# gps-breakout-mk-1_3.net
KiCad netlist of a schematic drawn in EAGLE
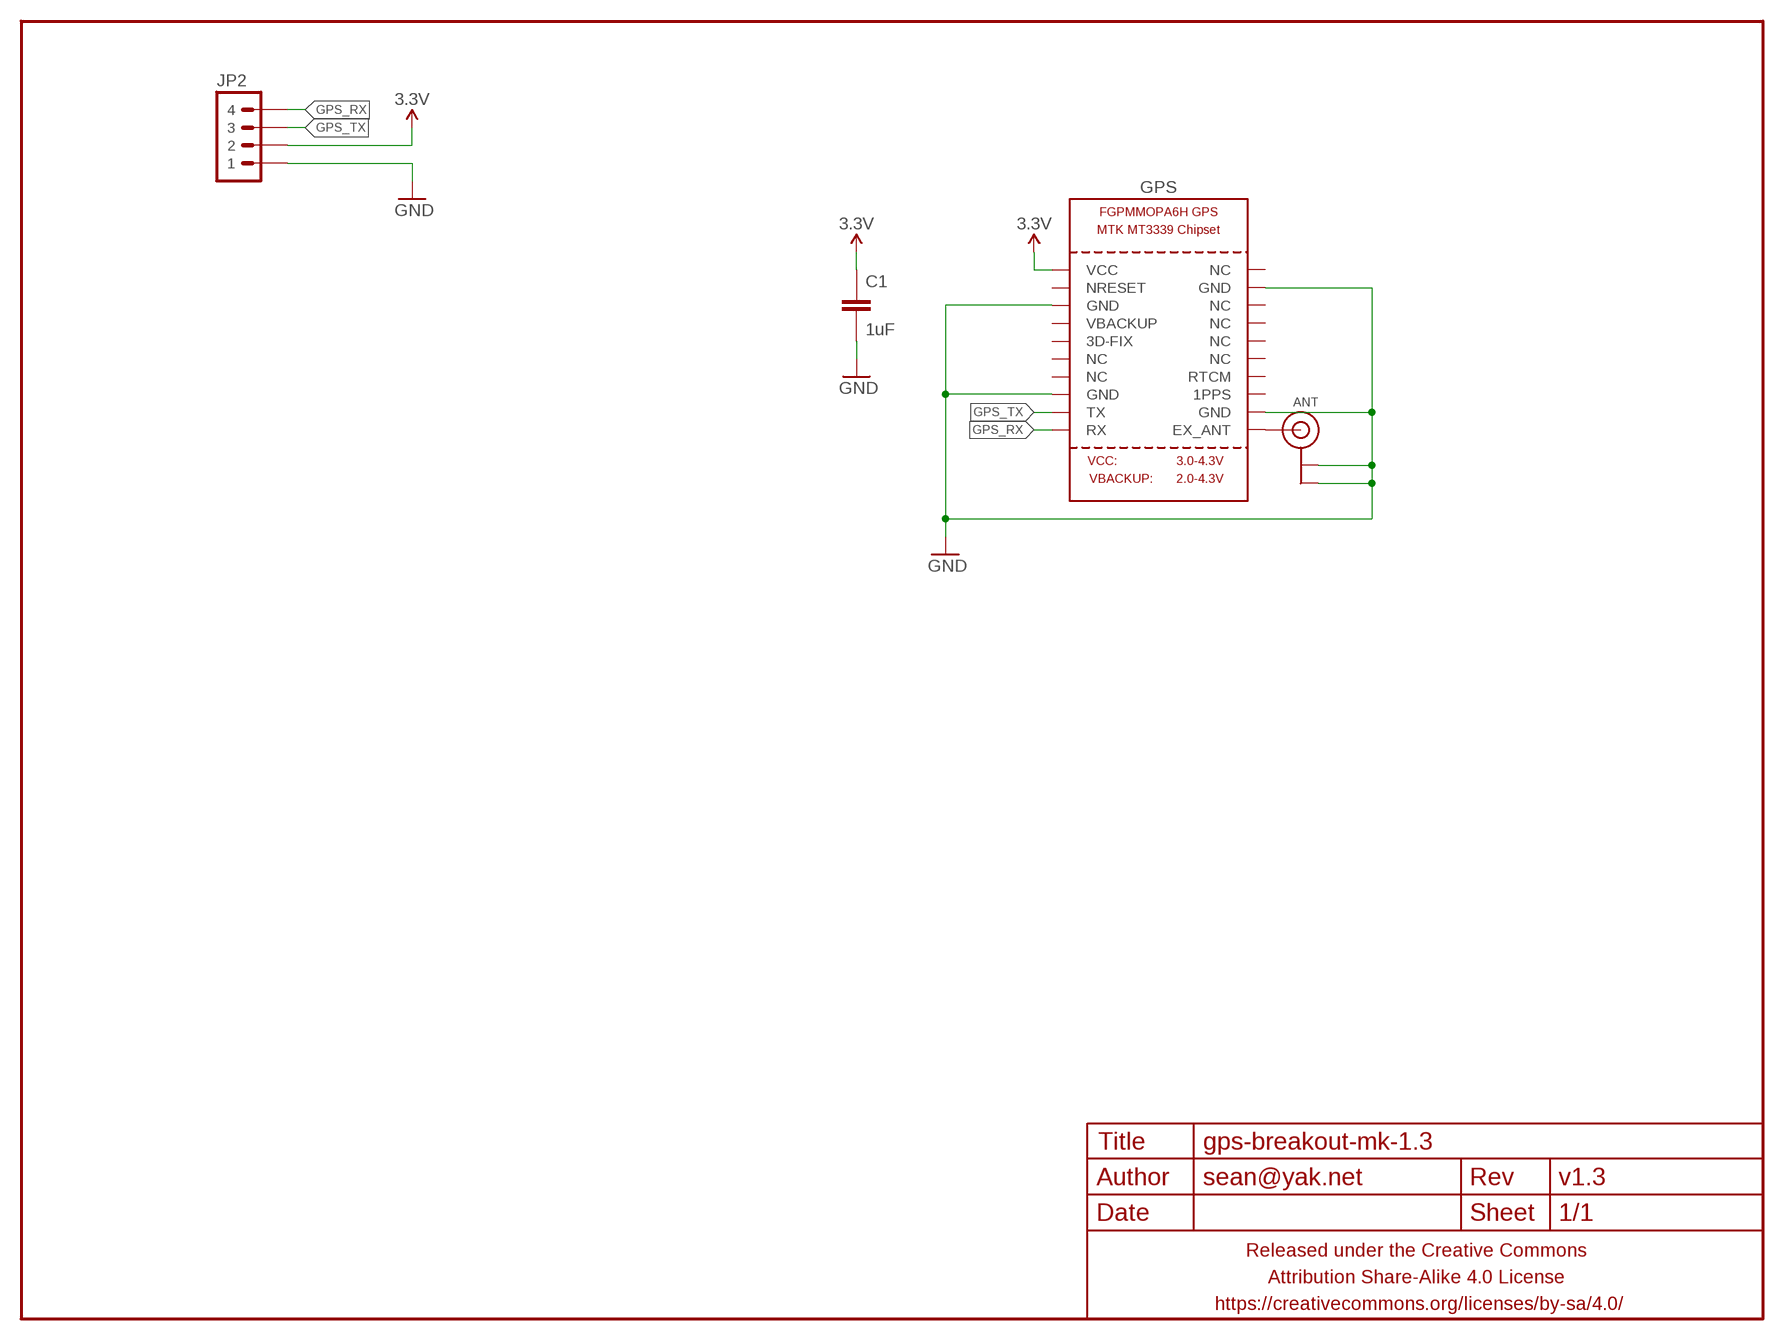
[diagram p0: schematic, sheet 1]

(export (version "E")
  (design (tool "Eeschema 10.0.6"))
  (components
    (comp (ref "ANT")
      (value "ANTENNAUFL")
      (footprint "eagle-import:U.FL")
      (libsource (lib "eagle-import") (part "ANTENNAUFL"))
    )
    (comp (ref "C1")
      (value "1uF")
      (footprint "eagle-import:C0603-TIGHTER")
      (libsource (lib "eagle-import") (part "CAPACITOR-CERAMICC0603-TIGHTER"))
    )
    (comp (ref "FRAME1")
      (value "FRAME-LETTERNO_PACKAGE")
      (footprint "eagle-import:DUMMY")
      (fields (field (name "DESIGNER") "sean@yak.net") (field (name "VERSION") "v1.3"))
      (libsource (lib "eagle-import") (part "FRAME-LETTERNO_PACKAGE"))
    )
    (comp (ref "GPS")
      (value "GPS_FGPMMOPA6H")
      (footprint "eagle-import:FGPMMOPA6H")
      (libsource (lib "eagle-import") (part "GPS_FGPMMOPA6H"))
    )
    (comp (ref "JP2")
      (value "M04SMD-FEMALE")
      (footprint "eagle-import:1X04-SMD-FEMALE-RA")
      (libsource (lib "eagle-import") (part "M04SMD-FEMALE"))
    )
  )
  (nets
    (net (code "1") (name "3.3V") (class "Default")
      (node (ref "C1") (pin "1") (pinfunction "1_1") (pintype "passive"))
      (node (ref "GPS") (pin "P$1") (pinfunction "VCC_P$1") (pintype "bidirectional"))
      (node (ref "JP2") (pin "P$2") (pinfunction "2_P$2") (pintype "passive"))
    )
    (net (code "2") (name "GND") (class "Default")
      (node (ref "ANT") (pin "1") (pinfunction "GND_1") (pintype "passive"))
      (node (ref "ANT") (pin "2") (pinfunction "GND_2") (pintype "passive"))
      (node (ref "C1") (pin "2") (pinfunction "2_2") (pintype "passive"))
      (node (ref "GPS") (pin "P$12") (pinfunction "GND_P$12") (pintype "bidirectional"))
      (node (ref "GPS") (pin "P$19") (pinfunction "GND_P$19") (pintype "bidirectional"))
      (node (ref "GPS") (pin "P$3") (pinfunction "GND_P$3") (pintype "bidirectional"))
      (node (ref "GPS") (pin "P$8") (pinfunction "GND_P$8") (pintype "bidirectional"))
      (node (ref "JP2") (pin "P$1") (pinfunction "1_P$1") (pintype "passive"))
    )
    (net (code "3") (name "GPS_RX") (class "Default")
      (node (ref "GPS") (pin "P$10") (pinfunction "RX_P$10") (pintype "bidirectional"))
      (node (ref "JP2") (pin "P$4") (pinfunction "4_P$4") (pintype "passive"))
    )
    (net (code "4") (name "GPS_TX") (class "Default")
      (node (ref "GPS") (pin "P$9") (pinfunction "TX_P$9") (pintype "bidirectional"))
      (node (ref "JP2") (pin "P$3") (pinfunction "3_P$3") (pintype "passive"))
    )
    (net (code "5") (name "Net-(ANT-SIGNAL)") (class "Default")
      (node (ref "ANT") (pin "3") (pinfunction "SIGNAL_3") (pintype "passive"))
      (node (ref "GPS") (pin "P$11") (pinfunction "EX_ANT_P$11") (pintype "bidirectional"))
    )
    (net (code "6") (name "unconnected-(GPS-1PPS-PadP$13)") (class "Default")
      (node (ref "GPS") (pin "P$13") (pinfunction "1PPS_P$13") (pintype "bidirectional"))
    )
    (net (code "7") (name "unconnected-(GPS-3D-FIX-PadP$5)") (class "Default")
      (node (ref "GPS") (pin "P$5") (pinfunction "3D-FIX_P$5") (pintype "bidirectional"))
    )
    (net (code "8") (name "unconnected-(GPS-NC-PadP$6)") (class "Default")
      (node (ref "GPS") (pin "P$6") (pinfunction "NC_P$6") (pintype "bidirectional"))
    )
    (net (code "9") (name "unconnected-(GPS-NC-PadP$7)") (class "Default")
      (node (ref "GPS") (pin "P$7") (pinfunction "NC_P$7") (pintype "bidirectional"))
    )
    (net (code "10") (name "unconnected-(GPS-NC-PadP$15)") (class "Default")
      (node (ref "GPS") (pin "P$15") (pinfunction "NC_P$15") (pintype "bidirectional"))
    )
    (net (code "11") (name "unconnected-(GPS-NC-PadP$16)") (class "Default")
      (node (ref "GPS") (pin "P$16") (pinfunction "NC_P$16") (pintype "bidirectional"))
    )
    (net (code "12") (name "unconnected-(GPS-NC-PadP$17)") (class "Default")
      (node (ref "GPS") (pin "P$17") (pinfunction "NC_P$17") (pintype "bidirectional"))
    )
    (net (code "13") (name "unconnected-(GPS-NC-PadP$18)") (class "Default")
      (node (ref "GPS") (pin "P$18") (pinfunction "NC_P$18") (pintype "bidirectional"))
    )
    (net (code "14") (name "unconnected-(GPS-NC-PadP$20)") (class "Default")
      (node (ref "GPS") (pin "P$20") (pinfunction "NC_P$20") (pintype "bidirectional"))
    )
    (net (code "15") (name "unconnected-(GPS-NRESET-PadP$2)") (class "Default")
      (node (ref "GPS") (pin "P$2") (pinfunction "NRESET_P$2") (pintype "bidirectional"))
    )
    (net (code "16") (name "unconnected-(GPS-RTCM-PadP$14)") (class "Default")
      (node (ref "GPS") (pin "P$14") (pinfunction "RTCM_P$14") (pintype "bidirectional"))
    )
    (net (code "17") (name "unconnected-(GPS-VBACKUP-PadP$4)") (class "Default")
      (node (ref "GPS") (pin "P$4") (pinfunction "VBACKUP_P$4") (pintype "bidirectional"))
    )
  )
)
